# AFE.net
KiCad netlist of a schematic drawn in Altium Designer
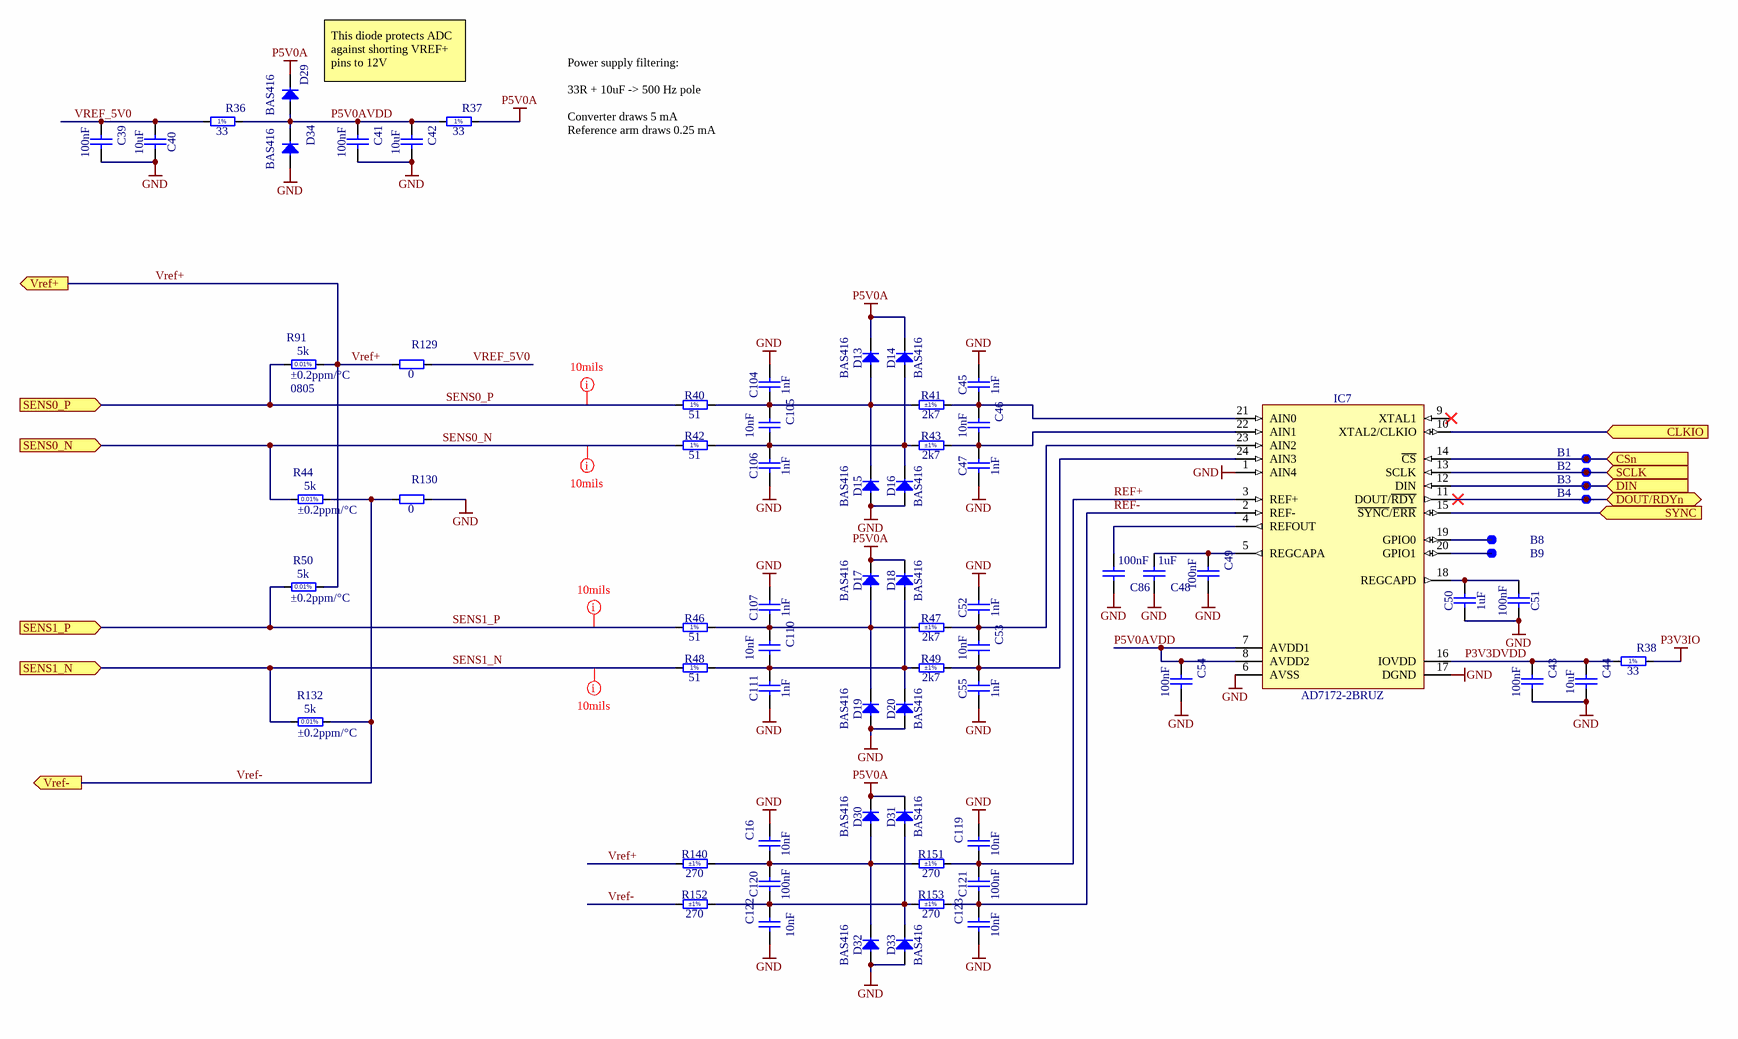
[diagram p0: AFE.SchDoc]

(export (version "E")
  (design (tool "Eeschema 10.0.6"))
  (components
    (comp (ref "B1")
      (value "SMD Pad")
      (footprint "C100")
      (description "Through Hole Pad")
      (fields (field (name "PART NUMBER") "SMD_PAD_D1MM") (field (name "AUTHOR") "CERN DEM JLC"))
      (libsource (lib "Eletro-mechanical") (part "Single SMD Pad (Round)"))
    )
    (comp (ref "B2")
      (value "SMD Pad")
      (footprint "C100")
      (description "Through Hole Pad")
      (fields (field (name "PART NUMBER") "SMD_PAD_D1MM") (field (name "AUTHOR") "CERN DEM JLC"))
      (libsource (lib "Eletro-mechanical") (part "Single SMD Pad (Round)"))
    )
    (comp (ref "B3")
      (value "SMD Pad")
      (footprint "C100")
      (description "Through Hole Pad")
      (fields (field (name "PART NUMBER") "SMD_PAD_D1MM") (field (name "AUTHOR") "CERN DEM JLC"))
      (libsource (lib "Eletro-mechanical") (part "Single SMD Pad (Round)"))
    )
    (comp (ref "B4")
      (value "SMD Pad")
      (footprint "C100")
      (description "Through Hole Pad")
      (fields (field (name "PART NUMBER") "SMD_PAD_D1MM") (field (name "AUTHOR") "CERN DEM JLC"))
      (libsource (lib "Eletro-mechanical") (part "Single SMD Pad (Round)"))
    )
    (comp (ref "B8")
      (value "SMD Pad")
      (footprint "C100")
      (description "Through Hole Pad")
      (fields (field (name "PART NUMBER") "SMD_PAD_D1MM") (field (name "AUTHOR") "CERN DEM JLC"))
      (libsource (lib "Eletro-mechanical") (part "Single SMD Pad (Round)"))
    )
    (comp (ref "B9")
      (value "SMD Pad")
      (footprint "C100")
      (description "Through Hole Pad")
      (fields (field (name "PART NUMBER") "SMD_PAD_D1MM") (field (name "AUTHOR") "CERN DEM JLC"))
      (libsource (lib "Eletro-mechanical") (part "Single SMD Pad (Round)"))
    )
    (comp (ref "C16")
      (value "10nF")
      (footprint "CAPC1608X87N")
      (description "Non-polarised capacitor")
      (fields
        (field (name "PART NUMBER") "CC0603_10NF_50V_5%_C0G")
        (field (name "VOLTAGE") "50V")
        (field (name "AUTHOR") "CERN DEM JLC")
      )
      (libsource (lib "Capacitors") (part "Capacitor - non polarized"))
    )
    (comp (ref "C39")
      (value "100nF")
      (footprint "CAPC1005X55N")
      (description "Non-polarised capacitor")
      (fields
        (field (name "PART NUMBER") "CC0402_100NF_16V_10%_X5R")
        (field (name "VOLTAGE") "16V")
        (field (name "AUTHOR") "CERN DEM JLC")
      )
      (libsource (lib "Capacitors") (part "Capacitor - non polarized"))
    )
    (comp (ref "C40")
      (value "10uF")
      (footprint "CAPC2012X135N")
      (description "Non-polarised capacitor")
      (fields
        (field (name "PART NUMBER") "CC0805_10UF_16V_10%_X5R")
        (field (name "VOLTAGE") "16V")
        (field (name "AUTHOR") "CERN DEM JLC")
      )
      (libsource (lib "Capacitors") (part "Capacitor - non polarized"))
    )
    (comp (ref "C41")
      (value "100nF")
      (footprint "CAPC1005X55N")
      (description "Non-polarised capacitor")
      (fields
        (field (name "PART NUMBER") "CC0402_100NF_16V_10%_X5R")
        (field (name "VOLTAGE") "16V")
        (field (name "AUTHOR") "CERN DEM JLC")
      )
      (libsource (lib "Capacitors") (part "Capacitor - non polarized"))
    )
    (comp (ref "C42")
      (value "10uF")
      (footprint "CAPC2012X135N")
      (description "Non-polarised capacitor")
      (fields
        (field (name "PART NUMBER") "CC0805_10UF_16V_10%_X5R")
        (field (name "VOLTAGE") "16V")
        (field (name "AUTHOR") "CERN DEM JLC")
      )
      (libsource (lib "Capacitors") (part "Capacitor - non polarized"))
    )
    (comp (ref "C43")
      (value "100nF")
      (footprint "CAPC1005X55N")
      (description "Non-polarised capacitor")
      (fields
        (field (name "PART NUMBER") "CC0402_100NF_16V_10%_X5R")
        (field (name "VOLTAGE") "16V")
        (field (name "AUTHOR") "CERN DEM JLC")
      )
      (libsource (lib "Capacitors") (part "Capacitor - non polarized"))
    )
    (comp (ref "C44")
      (value "10uF")
      (footprint "CAPC2012X135N")
      (description "Non-polarised capacitor")
      (fields
        (field (name "PART NUMBER") "CC0805_10UF_16V_10%_X5R")
        (field (name "VOLTAGE") "16V")
        (field (name "AUTHOR") "CERN DEM JLC")
      )
      (libsource (lib "Capacitors") (part "Capacitor - non polarized"))
    )
    (comp (ref "C45")
      (value "1nF")
      (footprint "CAPC1608X90N")
      (description "Non-polarised capacitor")
      (fields
        (field (name "PART NUMBER") "CC0603_1NF_50V_5%_NP0")
        (field (name "VOLTAGE") "50V")
        (field (name "AUTHOR") "CERN DEM JLC")
      )
      (libsource (lib "Capacitors") (part "Capacitor - non polarized"))
    )
    (comp (ref "C46")
      (value "10nF")
      (footprint "CAPC1608X87N")
      (description "Non-polarised capacitor")
      (fields
        (field (name "PART NUMBER") "CC0603_10NF_50V_5%_C0G")
        (field (name "VOLTAGE") "50V")
        (field (name "AUTHOR") "CERN DEM JLC")
      )
      (libsource (lib "Capacitors") (part "Capacitor - non polarized"))
    )
    (comp (ref "C47")
      (value "1nF")
      (footprint "CAPC1608X90N")
      (description "Non-polarised capacitor")
      (fields
        (field (name "PART NUMBER") "CC0603_1NF_50V_5%_NP0")
        (field (name "VOLTAGE") "50V")
        (field (name "AUTHOR") "CERN DEM JLC")
      )
      (libsource (lib "Capacitors") (part "Capacitor - non polarized"))
    )
    (comp (ref "C48")
      (value "1uF")
      (footprint "CAPC1608X87N")
      (description "Non-polarised capacitor")
      (fields
        (field (name "PART NUMBER") "CC0603_1UF_25V_10%_X7R")
        (field (name "VOLTAGE") "25V")
        (field (name "AUTHOR") "CERN DEM JLC")
      )
      (libsource (lib "Capacitors") (part "Capacitor - non polarized"))
    )
    (comp (ref "C49")
      (value "100nF")
      (footprint "CAPC1005X55N")
      (description "Non-polarised capacitor")
      (fields
        (field (name "PART NUMBER") "CC0402_100NF_16V_10%_X5R")
        (field (name "VOLTAGE") "16V")
        (field (name "AUTHOR") "CERN DEM JLC")
      )
      (libsource (lib "Capacitors") (part "Capacitor - non polarized"))
    )
    (comp (ref "C50")
      (value "1uF")
      (footprint "CAPC1608X87N")
      (description "Non-polarised capacitor")
      (fields
        (field (name "PART NUMBER") "CC0603_1UF_25V_10%_X7R")
        (field (name "VOLTAGE") "25V")
        (field (name "AUTHOR") "CERN DEM JLC")
      )
      (libsource (lib "Capacitors") (part "Capacitor - non polarized"))
    )
    (comp (ref "C51")
      (value "100nF")
      (footprint "CAPC1005X55N")
      (description "Non-polarised capacitor")
      (fields
        (field (name "PART NUMBER") "CC0402_100NF_16V_10%_X5R")
        (field (name "VOLTAGE") "16V")
        (field (name "AUTHOR") "CERN DEM JLC")
      )
      (libsource (lib "Capacitors") (part "Capacitor - non polarized"))
    )
    (comp (ref "C52")
      (value "1nF")
      (footprint "CAPC1608X90N")
      (description "Non-polarised capacitor")
      (fields
        (field (name "PART NUMBER") "CC0603_1NF_50V_5%_NP0")
        (field (name "VOLTAGE") "50V")
        (field (name "AUTHOR") "CERN DEM JLC")
      )
      (libsource (lib "Capacitors") (part "Capacitor - non polarized"))
    )
    (comp (ref "C53")
      (value "10nF")
      (footprint "CAPC1608X87N")
      (description "Non-polarised capacitor")
      (fields
        (field (name "PART NUMBER") "CC0603_10NF_50V_5%_C0G")
        (field (name "VOLTAGE") "50V")
        (field (name "AUTHOR") "CERN DEM JLC")
      )
      (libsource (lib "Capacitors") (part "Capacitor - non polarized"))
    )
    (comp (ref "C54")
      (value "100nF")
      (footprint "CAPC1005X55N")
      (description "Non-polarised capacitor")
      (fields
        (field (name "PART NUMBER") "CC0402_100NF_16V_10%_X5R")
        (field (name "VOLTAGE") "16V")
        (field (name "AUTHOR") "CERN DEM JLC")
      )
      (libsource (lib "Capacitors") (part "Capacitor - non polarized"))
    )
    (comp (ref "C55")
      (value "1nF")
      (footprint "CAPC1608X90N")
      (description "Non-polarised capacitor")
      (fields
        (field (name "PART NUMBER") "CC0603_1NF_50V_5%_NP0")
        (field (name "VOLTAGE") "50V")
        (field (name "AUTHOR") "CERN DEM JLC")
      )
      (libsource (lib "Capacitors") (part "Capacitor - non polarized"))
    )
    (comp (ref "C86")
      (value "100nF")
      (footprint "CAPC1005X55N")
      (description "Non-polarised capacitor")
      (fields
        (field (name "PART NUMBER") "CC0402_100NF_16V_10%_X5R")
        (field (name "VOLTAGE") "16V")
        (field (name "AUTHOR") "CERN DEM JLC")
      )
      (libsource (lib "Capacitors") (part "Capacitor - non polarized"))
    )
    (comp (ref "C104")
      (value "1nF")
      (footprint "CAPC1608X90N")
      (description "Non-polarised capacitor")
      (fields
        (field (name "PART NUMBER") "CC0603_1NF_50V_5%_NP0")
        (field (name "VOLTAGE") "50V")
        (field (name "AUTHOR") "CERN DEM JLC")
      )
      (libsource (lib "Capacitors") (part "Capacitor - non polarized"))
    )
    (comp (ref "C105")
      (value "10nF")
      (footprint "CAPC1608X87N")
      (description "Non-polarised capacitor")
      (fields
        (field (name "PART NUMBER") "CC0603_10NF_50V_5%_C0G")
        (field (name "VOLTAGE") "50V")
        (field (name "AUTHOR") "CERN DEM JLC")
      )
      (libsource (lib "Capacitors") (part "Capacitor - non polarized"))
    )
    (comp (ref "C106")
      (value "1nF")
      (footprint "CAPC1608X90N")
      (description "Non-polarised capacitor")
      (fields
        (field (name "PART NUMBER") "CC0603_1NF_50V_5%_NP0")
        (field (name "VOLTAGE") "50V")
        (field (name "AUTHOR") "CERN DEM JLC")
      )
      (libsource (lib "Capacitors") (part "Capacitor - non polarized"))
    )
    (comp (ref "C107")
      (value "1nF")
      (footprint "CAPC1608X90N")
      (description "Non-polarised capacitor")
      (fields
        (field (name "PART NUMBER") "CC0603_1NF_50V_5%_NP0")
        (field (name "VOLTAGE") "50V")
        (field (name "AUTHOR") "CERN DEM JLC")
      )
      (libsource (lib "Capacitors") (part "Capacitor - non polarized"))
    )
    (comp (ref "C110")
      (value "10nF")
      (footprint "CAPC1608X87N")
      (description "Non-polarised capacitor")
      (fields
        (field (name "PART NUMBER") "CC0603_10NF_50V_5%_C0G")
        (field (name "VOLTAGE") "50V")
        (field (name "AUTHOR") "CERN DEM JLC")
      )
      (libsource (lib "Capacitors") (part "Capacitor - non polarized"))
    )
    (comp (ref "C111")
      (value "1nF")
      (footprint "CAPC1608X90N")
      (description "Non-polarised capacitor")
      (fields
        (field (name "PART NUMBER") "CC0603_1NF_50V_5%_NP0")
        (field (name "VOLTAGE") "50V")
        (field (name "AUTHOR") "CERN DEM JLC")
      )
      (libsource (lib "Capacitors") (part "Capacitor - non polarized"))
    )
    (comp (ref "C119")
      (value "10nF")
      (footprint "CAPC1608X87N")
      (description "Non-polarised capacitor")
      (fields
        (field (name "PART NUMBER") "CC0603_10NF_50V_5%_C0G")
        (field (name "VOLTAGE") "50V")
        (field (name "AUTHOR") "CERN DEM JLC")
      )
      (libsource (lib "Capacitors") (part "Capacitor - non polarized"))
    )
    (comp (ref "C120")
      (value "100nF")
      (footprint "CAPC1608X87N")
      (description "Non-polarised capacitor")
      (fields
        (field (name "PART NUMBER") "CC0603_100NF_50V_10%_X5R")
        (field (name "VOLTAGE") "50V")
        (field (name "AUTHOR") "CERN DEM MR")
      )
      (libsource (lib "Capacitors") (part "Capacitor - non polarized"))
    )
    (comp (ref "C121")
      (value "100nF")
      (footprint "CAPC1608X87N")
      (description "Non-polarised capacitor")
      (fields
        (field (name "PART NUMBER") "CC0603_100NF_50V_10%_X5R")
        (field (name "VOLTAGE") "50V")
        (field (name "AUTHOR") "CERN DEM MR")
      )
      (libsource (lib "Capacitors") (part "Capacitor - non polarized"))
    )
    (comp (ref "C122")
      (value "10nF")
      (footprint "CAPC1608X87N")
      (description "Non-polarised capacitor")
      (fields
        (field (name "PART NUMBER") "CC0603_10NF_50V_5%_C0G")
        (field (name "VOLTAGE") "50V")
        (field (name "AUTHOR") "CERN DEM JLC")
      )
      (libsource (lib "Capacitors") (part "Capacitor - non polarized"))
    )
    (comp (ref "C123")
      (value "10nF")
      (footprint "CAPC1608X87N")
      (description "Non-polarised capacitor")
      (fields
        (field (name "PART NUMBER") "CC0603_10NF_50V_5%_C0G")
        (field (name "VOLTAGE") "50V")
        (field (name "AUTHOR") "CERN DEM JLC")
      )
      (libsource (lib "Capacitors") (part "Capacitor - non polarized"))
    )
    (comp (ref "D13")
      (value "BAS416")
      (footprint "SOD2512X110N")
      (description "Diode")
      (fields
        (field (name "VOLTAGE") "75V")
        (field (name "POWER") "200mA")
        (field (name "AUTHOR") "CERN DEM JLC")
      )
      (libsource (lib "ICs And Semiconductors") (part "Diode"))
    )
    (comp (ref "D14")
      (value "BAS416")
      (footprint "SOD2512X110N")
      (description "Diode")
      (fields
        (field (name "VOLTAGE") "75V")
        (field (name "POWER") "200mA")
        (field (name "AUTHOR") "CERN DEM JLC")
      )
      (libsource (lib "ICs And Semiconductors") (part "Diode"))
    )
    (comp (ref "D15")
      (value "BAS416")
      (footprint "SOD2512X110N")
      (description "Diode")
      (fields
        (field (name "VOLTAGE") "75V")
        (field (name "POWER") "200mA")
        (field (name "AUTHOR") "CERN DEM JLC")
      )
      (libsource (lib "ICs And Semiconductors") (part "Diode"))
    )
    (comp (ref "D16")
      (value "BAS416")
      (footprint "SOD2512X110N")
      (description "Diode")
      (fields
        (field (name "VOLTAGE") "75V")
        (field (name "POWER") "200mA")
        (field (name "AUTHOR") "CERN DEM JLC")
      )
      (libsource (lib "ICs And Semiconductors") (part "Diode"))
    )
    (comp (ref "D17")
      (value "BAS416")
      (footprint "SOD2512X110N")
      (description "Diode")
      (fields
        (field (name "VOLTAGE") "75V")
        (field (name "POWER") "200mA")
        (field (name "AUTHOR") "CERN DEM JLC")
      )
      (libsource (lib "ICs And Semiconductors") (part "Diode"))
    )
    (comp (ref "D18")
      (value "BAS416")
      (footprint "SOD2512X110N")
      (description "Diode")
      (fields
        (field (name "VOLTAGE") "75V")
        (field (name "POWER") "200mA")
        (field (name "AUTHOR") "CERN DEM JLC")
      )
      (libsource (lib "ICs And Semiconductors") (part "Diode"))
    )
    (comp (ref "D19")
      (value "BAS416")
      (footprint "SOD2512X110N")
      (description "Diode")
      (fields
        (field (name "VOLTAGE") "75V")
        (field (name "POWER") "200mA")
        (field (name "AUTHOR") "CERN DEM JLC")
      )
      (libsource (lib "ICs And Semiconductors") (part "Diode"))
    )
    (comp (ref "D20")
      (value "BAS416")
      (footprint "SOD2512X110N")
      (description "Diode")
      (fields
        (field (name "VOLTAGE") "75V")
        (field (name "POWER") "200mA")
        (field (name "AUTHOR") "CERN DEM JLC")
      )
      (libsource (lib "ICs And Semiconductors") (part "Diode"))
    )
    (comp (ref "D29")
      (value "BAS416")
      (footprint "SOD2512X110N")
      (description "Diode")
      (fields
        (field (name "VOLTAGE") "75V")
        (field (name "POWER") "200mA")
        (field (name "AUTHOR") "CERN DEM JLC")
      )
      (libsource (lib "ICs And Semiconductors") (part "Diode"))
    )
    (comp (ref "D30")
      (value "BAS416")
      (footprint "SOD2512X110N")
      (description "Diode")
      (fields
        (field (name "VOLTAGE") "75V")
        (field (name "POWER") "200mA")
        (field (name "AUTHOR") "CERN DEM JLC")
      )
      (libsource (lib "ICs And Semiconductors") (part "Diode"))
    )
    (comp (ref "D31")
      (value "BAS416")
      (footprint "SOD2512X110N")
      (description "Diode")
      (fields
        (field (name "VOLTAGE") "75V")
        (field (name "POWER") "200mA")
        (field (name "AUTHOR") "CERN DEM JLC")
      )
      (libsource (lib "ICs And Semiconductors") (part "Diode"))
    )
    (comp (ref "D32")
      (value "BAS416")
      (footprint "SOD2512X110N")
      (description "Diode")
      (fields
        (field (name "VOLTAGE") "75V")
        (field (name "POWER") "200mA")
        (field (name "AUTHOR") "CERN DEM JLC")
      )
      (libsource (lib "ICs And Semiconductors") (part "Diode"))
    )
    (comp (ref "D33")
      (value "BAS416")
      (footprint "SOD2512X110N")
      (description "Diode")
      (fields
        (field (name "VOLTAGE") "75V")
        (field (name "POWER") "200mA")
        (field (name "AUTHOR") "CERN DEM JLC")
      )
      (libsource (lib "ICs And Semiconductors") (part "Diode"))
    )
    (comp (ref "D34")
      (value "BAS416")
      (footprint "SOD2512X110N")
      (description "Diode")
      (fields
        (field (name "VOLTAGE") "75V")
        (field (name "POWER") "200mA")
        (field (name "AUTHOR") "CERN DEM JLC")
      )
      (libsource (lib "ICs And Semiconductors") (part "Diode"))
    )
    (comp (ref "IC7")
      (value "AD7172-2BRUZ")
      (footprint "SOP65P640X120-24N")
      (description "32-Bit, 10 kSPS, Sigma-Delta ADC with 100 µs Settling and True Rail-to-Rail Buffers")
      (fields (field (name "MANUFACTURER") "ANALOG DEVICES") (field (name "AUTHOR") "GK"))
      (libsource (lib "LIBRARY_SCH") (part "ADC_AD7172-2"))
    )
    (comp (ref "R36")
      (value "33")
      (footprint "RESC1005X40N")
      (description "Resistor - 1%")
      (fields
        (field (name "PART NUMBER") "R0402_33R_1%_0.0625W_100PPM")
        (field (name "POWER") "0.0625W")
        (field (name "AUTHOR") "CERN DEM JLC")
      )
      (libsource (lib "Resistors") (part "Resistor - 1%"))
    )
    (comp (ref "R37")
      (value "33")
      (footprint "RESC1005X40N")
      (description "Resistor - 1%")
      (fields
        (field (name "PART NUMBER") "R0402_33R_1%_0.0625W_100PPM")
        (field (name "POWER") "0.0625W")
        (field (name "AUTHOR") "CERN DEM JLC")
      )
      (libsource (lib "Resistors") (part "Resistor - 1%"))
    )
    (comp (ref "R38")
      (value "33")
      (footprint "RESC1005X40N")
      (description "Resistor - 1%")
      (fields
        (field (name "PART NUMBER") "R0402_33R_1%_0.0625W_100PPM")
        (field (name "POWER") "0.0625W")
        (field (name "AUTHOR") "CERN DEM JLC")
      )
      (libsource (lib "Resistors") (part "Resistor - 1%"))
    )
    (comp (ref "R40")
      (value "51")
      (footprint "RESC1005X40N")
      (description "Resistor - 1%")
      (fields
        (field (name "PART NUMBER") "R0402_51R_1%_0.0625W_100PPM")
        (field (name "POWER") "0.0625W")
        (field (name "AUTHOR") "CERN DEM JLC")
      )
      (libsource (lib "Resistors") (part "Resistor - 1%"))
    )
    (comp (ref "R41")
      (value "2k7")
      (footprint "RESC1005X40N")
      (description "Resistor - 1%")
      (fields
        (field (name "TOLERANCE") "±1%")
        (field (name "PART NUMBER") "R0402_2K7_1%_0.0625W_100PPM")
        (field (name "POWER") "0.0625W")
        (field (name "AUTHOR") "CERN DEM JLC")
      )
      (libsource (lib "Resistors") (part "Resistor - 1%"))
    )
    (comp (ref "R42")
      (value "51")
      (footprint "RESC1005X40N")
      (description "Resistor - 1%")
      (fields
        (field (name "PART NUMBER") "R0402_51R_1%_0.0625W_100PPM")
        (field (name "POWER") "0.0625W")
        (field (name "AUTHOR") "CERN DEM JLC")
      )
      (libsource (lib "Resistors") (part "Resistor - 1%"))
    )
    (comp (ref "R43")
      (value "2k7")
      (footprint "RESC1005X40N")
      (description "Resistor - 1%")
      (fields
        (field (name "TOLERANCE") "±1%")
        (field (name "PART NUMBER") "R0402_2K7_1%_0.0625W_100PPM")
        (field (name "POWER") "0.0625W")
        (field (name "AUTHOR") "CERN DEM JLC")
      )
      (libsource (lib "Resistors") (part "Resistor - 1%"))
    )
    (comp (ref "R44")
      (value "5k")
      (footprint "RESC2013X64N")
      (description "Resistor - 0.01%")
      (fields
        (field (name "PART NUMBER") "R0805_5K_0.01%_0.2W_0.2PPM_VISHAY_VSMP")
        (field (name "POWER") "0.2W")
        (field (name "TC") "±0.2ppm/°C")
        (field (name "AUTHOR") "CERN DEM JLC")
      )
      (libsource (lib "Resistors") (part "Resistor - 0.01%"))
    )
    (comp (ref "R46")
      (value "51")
      (footprint "RESC1005X40N")
      (description "Resistor - 1%")
      (fields
        (field (name "PART NUMBER") "R0402_51R_1%_0.0625W_100PPM")
        (field (name "POWER") "0.0625W")
        (field (name "AUTHOR") "CERN DEM JLC")
      )
      (libsource (lib "Resistors") (part "Resistor - 1%"))
    )
    (comp (ref "R47")
      (value "2k7")
      (footprint "RESC1005X40N")
      (description "Resistor - 1%")
      (fields
        (field (name "TOLERANCE") "±1%")
        (field (name "PART NUMBER") "R0402_2K7_1%_0.0625W_100PPM")
        (field (name "POWER") "0.0625W")
        (field (name "AUTHOR") "CERN DEM JLC")
      )
      (libsource (lib "Resistors") (part "Resistor - 1%"))
    )
    (comp (ref "R48")
      (value "51")
      (footprint "RESC1005X40N")
      (description "Resistor - 1%")
      (fields
        (field (name "PART NUMBER") "R0402_51R_1%_0.0625W_100PPM")
        (field (name "POWER") "0.0625W")
        (field (name "AUTHOR") "CERN DEM JLC")
      )
      (libsource (lib "Resistors") (part "Resistor - 1%"))
    )
    (comp (ref "R49")
      (value "2k7")
      (footprint "RESC1005X40N")
      (description "Resistor - 1%")
      (fields
        (field (name "TOLERANCE") "±1%")
        (field (name "PART NUMBER") "R0402_2K7_1%_0.0625W_100PPM")
        (field (name "POWER") "0.0625W")
        (field (name "AUTHOR") "CERN DEM JLC")
      )
      (libsource (lib "Resistors") (part "Resistor - 1%"))
    )
    (comp (ref "R50")
      (value "5k")
      (footprint "RESC2013X64N")
      (description "Resistor - 0.01%")
      (fields
        (field (name "PART NUMBER") "R0805_5K_0.01%_0.2W_0.2PPM_VISHAY_VSMP")
        (field (name "POWER") "0.2W")
        (field (name "TC") "±0.2ppm/°C")
        (field (name "AUTHOR") "CERN DEM JLC")
      )
      (libsource (lib "Resistors") (part "Resistor - 0.01%"))
    )
    (comp (ref "R91")
      (value "5k")
      (footprint "RESC2013X64N")
      (description "Resistor - 0.01%")
      (fields
        (field (name "PART NUMBER") "R0805_5K_0.01%_0.2W_0.2PPM_VISHAY_VSMP")
        (field (name "POWER") "0.2W")
        (field (name "TC") "±0.2ppm/°C")
        (field (name "CASE") "0805")
        (field (name "AUTHOR") "CERN DEM JLC")
      )
      (libsource (lib "Resistors") (part "Resistor - 0.01%"))
    )
    (comp (ref "R129")
      (value "0")
      (footprint "RESC1608X55N")
      (description "Resistor")
      (fields
        (field (name "PART NUMBER") "R0603_0R_JUMPER")
        (field (name "MANUFACTURER") "GENERIC")
        (field (name "AUTHOR") "CERN DEM JLC")
      )
      (libsource (lib "Resistors") (part "Resistor"))
    )
    (comp (ref "R130")
      (value "0")
      (footprint "RESC1608X55N")
      (description "Resistor")
      (fields
        (field (name "PART NUMBER") "R0603_0R_JUMPER")
        (field (name "MANUFACTURER") "GENERIC")
        (field (name "AUTHOR") "CERN DEM JLC")
      )
      (libsource (lib "Resistors") (part "Resistor"))
    )
    (comp (ref "R132")
      (value "5k")
      (footprint "RESC2013X64N")
      (description "Resistor - 0.01%")
      (fields
        (field (name "PART NUMBER") "R0805_5K_0.01%_0.2W_0.2PPM_VISHAY_VSMP")
        (field (name "POWER") "0.2W")
        (field (name "TC") "±0.2ppm/°C")
        (field (name "AUTHOR") "CERN DEM JLC")
      )
      (libsource (lib "Resistors") (part "Resistor - 0.01%"))
    )
    (comp (ref "R140")
      (value "270")
      (footprint "RESC1005X40N")
      (description "Resistor - 1%")
      (fields
        (field (name "TOLERANCE") "±1%")
        (field (name "PART NUMBER") "R0402_270R_1%_0.0625W_100PPM")
        (field (name "POWER") "0.0625W")
        (field (name "AUTHOR") "CERN DEM JLC")
      )
      (libsource (lib "Resistors") (part "Resistor - 1%"))
    )
    (comp (ref "R151")
      (value "270")
      (footprint "RESC1005X40N")
      (description "Resistor - 1%")
      (fields
        (field (name "TOLERANCE") "±1%")
        (field (name "PART NUMBER") "R0402_270R_1%_0.0625W_100PPM")
        (field (name "POWER") "0.0625W")
        (field (name "AUTHOR") "CERN DEM JLC")
      )
      (libsource (lib "Resistors") (part "Resistor - 1%"))
    )
    (comp (ref "R152")
      (value "270")
      (footprint "RESC1005X40N")
      (description "Resistor - 1%")
      (fields
        (field (name "TOLERANCE") "±1%")
        (field (name "PART NUMBER") "R0402_270R_1%_0.0625W_100PPM")
        (field (name "POWER") "0.0625W")
        (field (name "AUTHOR") "CERN DEM JLC")
      )
      (libsource (lib "Resistors") (part "Resistor - 1%"))
    )
    (comp (ref "R153")
      (value "270")
      (footprint "RESC1005X40N")
      (description "Resistor - 1%")
      (fields
        (field (name "TOLERANCE") "±1%")
        (field (name "PART NUMBER") "R0402_270R_1%_0.0625W_100PPM")
        (field (name "POWER") "0.0625W")
        (field (name "AUTHOR") "CERN DEM JLC")
      )
      (libsource (lib "Resistors") (part "Resistor - 1%"))
    )
  )
  (nets
    (net (code "1") (name "/CLKIO") (class "Default")
      (node (ref "IC7") (pin "10") (pinfunction "XTAL2/CLKIO_10") (pintype "bidirectional"))
    )
    (net (code "2") (name "/CSn") (class "Default")
      (node (ref "B1") (pin "1") (pinfunction "1_1") (pintype "bidirectional"))
      (node (ref "IC7") (pin "14") (pinfunction "~{CS}_14") (pintype "input"))
    )
    (net (code "3") (name "/DIN") (class "Default")
      (node (ref "B3") (pin "1") (pinfunction "1_1") (pintype "bidirectional"))
      (node (ref "IC7") (pin "12") (pinfunction "DIN_12") (pintype "input"))
    )
    (net (code "4") (name "/DOUT{slash}RDYn") (class "Default")
      (node (ref "B4") (pin "1") (pinfunction "1_1") (pintype "bidirectional"))
      (node (ref "IC7") (pin "11") (pinfunction "DOUT/~{RDY}_11") (pintype "output"))
    )
    (net (code "5") (name "/P3V3DVDD") (class "Default")
      (node (ref "C43") (pin "1") (pinfunction "1_1") (pintype "passive"))
      (node (ref "C44") (pin "1") (pinfunction "1_1") (pintype "passive"))
      (node (ref "IC7") (pin "16") (pinfunction "IOVDD_16") (pintype "power_in"))
      (node (ref "R38") (pin "1") (pinfunction "1_1") (pintype "passive"))
    )
    (net (code "6") (name "/P5V0AVDD") (class "Default")
      (node (ref "C41") (pin "1") (pinfunction "1_1") (pintype "passive"))
      (node (ref "C42") (pin "1") (pinfunction "1_1") (pintype "passive"))
      (node (ref "C54") (pin "1") (pinfunction "1_1") (pintype "passive"))
      (node (ref "D29") (pin "2") (pinfunction "A_2") (pintype "passive"))
      (node (ref "D34") (pin "1") (pinfunction "C_1") (pintype "passive"))
      (node (ref "IC7") (pin "7") (pinfunction "AVDD1_7") (pintype "power_in"))
      (node (ref "IC7") (pin "8") (pinfunction "AVDD2_8") (pintype "power_in"))
      (node (ref "R36") (pin "2") (pinfunction "2_2") (pintype "passive"))
      (node (ref "R37") (pin "1") (pinfunction "1_1") (pintype "passive"))
    )
    (net (code "7") (name "/REF+") (class "Default")
      (node (ref "C119") (pin "1") (pinfunction "1_1") (pintype "passive"))
      (node (ref "C121") (pin "2") (pinfunction "2_2") (pintype "passive"))
      (node (ref "IC7") (pin "3") (pinfunction "REF+_3") (pintype "input"))
      (node (ref "R151") (pin "2") (pinfunction "2_2") (pintype "passive"))
    )
    (net (code "8") (name "/REF-") (class "Default")
      (node (ref "C121") (pin "1") (pinfunction "1_1") (pintype "passive"))
      (node (ref "C123") (pin "2") (pinfunction "2_2") (pintype "passive"))
      (node (ref "IC7") (pin "2") (pinfunction "REF-_2") (pintype "input"))
      (node (ref "R153") (pin "2") (pinfunction "2_2") (pintype "passive"))
    )
    (net (code "9") (name "/SCLK") (class "Default")
      (node (ref "B2") (pin "1") (pinfunction "1_1") (pintype "bidirectional"))
      (node (ref "IC7") (pin "13") (pinfunction "SCLK_13") (pintype "input"))
    )
    (net (code "10") (name "/SENS0_N") (class "Default")
      (node (ref "R42") (pin "1") (pinfunction "1_1") (pintype "passive"))
      (node (ref "R44") (pin "1") (pinfunction "1_1") (pintype "passive"))
    )
    (net (code "11") (name "/SENS0_P") (class "Default")
      (node (ref "R40") (pin "1") (pinfunction "1_1") (pintype "passive"))
      (node (ref "R91") (pin "1") (pinfunction "1_1") (pintype "passive"))
    )
    (net (code "12") (name "/SENS1_N") (class "Default")
      (node (ref "R132") (pin "1") (pinfunction "1_1") (pintype "passive"))
      (node (ref "R48") (pin "1") (pinfunction "1_1") (pintype "passive"))
    )
    (net (code "13") (name "/SENS1_P") (class "Default")
      (node (ref "R46") (pin "1") (pinfunction "1_1") (pintype "passive"))
      (node (ref "R50") (pin "1") (pinfunction "1_1") (pintype "passive"))
    )
    (net (code "14") (name "/SYNC") (class "Default")
      (node (ref "IC7") (pin "15") (pinfunction "~{SYNC}/~{ERR}_15") (pintype "bidirectional"))
    )
    (net (code "15") (name "/VREF_5V0") (class "Default")
      (node (ref "C39") (pin "1") (pinfunction "1_1") (pintype "passive"))
      (node (ref "C40") (pin "1") (pinfunction "1_1") (pintype "passive"))
      (node (ref "R129") (pin "2") (pinfunction "2_2") (pintype "passive"))
      (node (ref "R36") (pin "1") (pinfunction "1_1") (pintype "passive"))
    )
    (net (code "16") (name "/Vref+") (class "Default")
      (node (ref "R129") (pin "1") (pinfunction "1_1") (pintype "passive"))
      (node (ref "R140") (pin "1") (pinfunction "1_1") (pintype "passive"))
      (node (ref "R50") (pin "2") (pinfunction "2_2") (pintype "passive"))
      (node (ref "R91") (pin "2") (pinfunction "2_2") (pintype "passive"))
    )
    (net (code "17") (name "/Vref-") (class "Default")
      (node (ref "R130") (pin "1") (pinfunction "1_1") (pintype "passive"))
      (node (ref "R132") (pin "2") (pinfunction "2_2") (pintype "passive"))
      (node (ref "R152") (pin "1") (pinfunction "1_1") (pintype "passive"))
      (node (ref "R44") (pin "2") (pinfunction "2_2") (pintype "passive"))
    )
    (net (code "18") (name "GND") (class "Default")
      (node (ref "C104") (pin "2") (pinfunction "2_2") (pintype "passive"))
      (node (ref "C106") (pin "1") (pinfunction "1_1") (pintype "passive"))
      (node (ref "C107") (pin "2") (pinfunction "2_2") (pintype "passive"))
      (node (ref "C111") (pin "1") (pinfunction "1_1") (pintype "passive"))
      (node (ref "C119") (pin "2") (pinfunction "2_2") (pintype "passive"))
      (node (ref "C122") (pin "1") (pinfunction "1_1") (pintype "passive"))
      (node (ref "C123") (pin "1") (pinfunction "1_1") (pintype "passive"))
      (node (ref "C16") (pin "2") (pinfunction "2_2") (pintype "passive"))
      (node (ref "C39") (pin "2") (pinfunction "2_2") (pintype "passive"))
      (node (ref "C40") (pin "2") (pinfunction "2_2") (pintype "passive"))
      (node (ref "C41") (pin "2") (pinfunction "2_2") (pintype "passive"))
      (node (ref "C42") (pin "2") (pinfunction "2_2") (pintype "passive"))
      (node (ref "C43") (pin "2") (pinfunction "2_2") (pintype "passive"))
      (node (ref "C44") (pin "2") (pinfunction "2_2") (pintype "passive"))
      (node (ref "C45") (pin "2") (pinfunction "2_2") (pintype "passive"))
      (node (ref "C47") (pin "1") (pinfunction "1_1") (pintype "passive"))
      (node (ref "C48") (pin "1") (pinfunction "1_1") (pintype "passive"))
      (node (ref "C49") (pin "2") (pinfunction "2_2") (pintype "passive"))
      (node (ref "C50") (pin "1") (pinfunction "1_1") (pintype "passive"))
      (node (ref "C51") (pin "2") (pinfunction "2_2") (pintype "passive"))
      (node (ref "C52") (pin "2") (pinfunction "2_2") (pintype "passive"))
      (node (ref "C54") (pin "2") (pinfunction "2_2") (pintype "passive"))
      (node (ref "C55") (pin "1") (pinfunction "1_1") (pintype "passive"))
      (node (ref "C86") (pin "2") (pinfunction "2_2") (pintype "passive"))
      (node (ref "D15") (pin "2") (pinfunction "A_2") (pintype "passive"))
      (node (ref "D16") (pin "2") (pinfunction "A_2") (pintype "passive"))
      (node (ref "D19") (pin "2") (pinfunction "A_2") (pintype "passive"))
      (node (ref "D20") (pin "2") (pinfunction "A_2") (pintype "passive"))
      (node (ref "D32") (pin "2") (pinfunction "A_2") (pintype "passive"))
      (node (ref "D33") (pin "2") (pinfunction "A_2") (pintype "passive"))
      (node (ref "D34") (pin "2") (pinfunction "A_2") (pintype "passive"))
      (node (ref "IC7") (pin "1") (pinfunction "AIN4_1") (pintype "input"))
      (node (ref "IC7") (pin "17") (pinfunction "DGND_17") (pintype "power_in"))
      (node (ref "IC7") (pin "6") (pinfunction "AVSS_6") (pintype "power_in"))
      (node (ref "R130") (pin "2") (pinfunction "2_2") (pintype "passive"))
    )
    (net (code "19") (name "Net-(D13-A)") (class "Default")
      (node (ref "C104") (pin "1") (pinfunction "1_1") (pintype "passive"))
      (node (ref "C105") (pin "1") (pinfunction "1_1") (pintype "passive"))
      (node (ref "D13") (pin "2") (pinfunction "A_2") (pintype "passive"))
      (node (ref "D15") (pin "1") (pinfunction "C_1") (pintype "passive"))
      (node (ref "R40") (pin "2") (pinfunction "2_2") (pintype "passive"))
      (node (ref "R41") (pin "1") (pinfunction "1_1") (pintype "passive"))
    )
    (net (code "20") (name "Net-(D14-A)") (class "Default")
      (node (ref "C105") (pin "2") (pinfunction "2_2") (pintype "passive"))
      (node (ref "C106") (pin "2") (pinfunction "2_2") (pintype "passive"))
      (node (ref "D14") (pin "2") (pinfunction "A_2") (pintype "passive"))
      (node (ref "D16") (pin "1") (pinfunction "C_1") (pintype "passive"))
      (node (ref "R42") (pin "2") (pinfunction "2_2") (pintype "passive"))
      (node (ref "R43") (pin "1") (pinfunction "1_1") (pintype "passive"))
    )
    (net (code "21") (name "Net-(D17-A)") (class "Default")
      (node (ref "C107") (pin "1") (pinfunction "1_1") (pintype "passive"))
      (node (ref "C110") (pin "1") (pinfunction "1_1") (pintype "passive"))
      (node (ref "D17") (pin "2") (pinfunction "A_2") (pintype "passive"))
      (node (ref "D19") (pin "1") (pinfunction "C_1") (pintype "passive"))
      (node (ref "R46") (pin "2") (pinfunction "2_2") (pintype "passive"))
      (node (ref "R47") (pin "1") (pinfunction "1_1") (pintype "passive"))
    )
    (net (code "22") (name "Net-(D18-A)") (class "Default")
      (node (ref "C110") (pin "2") (pinfunction "2_2") (pintype "passive"))
      (node (ref "C111") (pin "2") (pinfunction "2_2") (pintype "passive"))
      (node (ref "D18") (pin "2") (pinfunction "A_2") (pintype "passive"))
      (node (ref "D20") (pin "1") (pinfunction "C_1") (pintype "passive"))
      (node (ref "R48") (pin "2") (pinfunction "2_2") (pintype "passive"))
      (node (ref "R49") (pin "1") (pinfunction "1_1") (pintype "passive"))
    )
    (net (code "23") (name "Net-(D30-A)") (class "Default")
      (node (ref "C120") (pin "2") (pinfunction "2_2") (pintype "passive"))
      (node (ref "C16") (pin "1") (pinfunction "1_1") (pintype "passive"))
      (node (ref "D30") (pin "2") (pinfunction "A_2") (pintype "passive"))
      (node (ref "D32") (pin "1") (pinfunction "C_1") (pintype "passive"))
      (node (ref "R140") (pin "2") (pinfunction "2_2") (pintype "passive"))
      (node (ref "R151") (pin "1") (pinfunction "1_1") (pintype "passive"))
    )
    (net (code "24") (name "Net-(D31-A)") (class "Default")
      (node (ref "C120") (pin "1") (pinfunction "1_1") (pintype "passive"))
      (node (ref "C122") (pin "2") (pinfunction "2_2") (pintype "passive"))
      (node (ref "D31") (pin "2") (pinfunction "A_2") (pintype "passive"))
      (node (ref "D33") (pin "1") (pinfunction "C_1") (pintype "passive"))
      (node (ref "R152") (pin "2") (pinfunction "2_2") (pintype "passive"))
      (node (ref "R153") (pin "1") (pinfunction "1_1") (pintype "passive"))
    )
    (net (code "25") (name "Net-(IC7-AIN0)") (class "Default")
      (node (ref "C45") (pin "1") (pinfunction "1_1") (pintype "passive"))
      (node (ref "C46") (pin "1") (pinfunction "1_1") (pintype "passive"))
      (node (ref "IC7") (pin "21") (pinfunction "AIN0_21") (pintype "input"))
      (node (ref "R41") (pin "2") (pinfunction "2_2") (pintype "passive"))
    )
    (net (code "26") (name "Net-(IC7-AIN1)") (class "Default")
      (node (ref "C46") (pin "2") (pinfunction "2_2") (pintype "passive"))
      (node (ref "C47") (pin "2") (pinfunction "2_2") (pintype "passive"))
      (node (ref "IC7") (pin "22") (pinfunction "AIN1_22") (pintype "input"))
      (node (ref "R43") (pin "2") (pinfunction "2_2") (pintype "passive"))
    )
    (net (code "27") (name "Net-(IC7-AIN2)") (class "Default")
      (node (ref "C52") (pin "1") (pinfunction "1_1") (pintype "passive"))
      (node (ref "C53") (pin "1") (pinfunction "1_1") (pintype "passive"))
      (node (ref "IC7") (pin "23") (pinfunction "AIN2_23") (pintype "input"))
      (node (ref "R47") (pin "2") (pinfunction "2_2") (pintype "passive"))
    )
    (net (code "28") (name "Net-(IC7-AIN3)") (class "Default")
      (node (ref "C53") (pin "2") (pinfunction "2_2") (pintype "passive"))
      (node (ref "C55") (pin "2") (pinfunction "2_2") (pintype "passive"))
      (node (ref "IC7") (pin "24") (pinfunction "AIN3_24") (pintype "input"))
      (node (ref "R49") (pin "2") (pinfunction "2_2") (pintype "passive"))
    )
    (net (code "29") (name "Net-(IC7-GPIO0)") (class "Default")
      (node (ref "B8") (pin "1") (pinfunction "1_1") (pintype "bidirectional"))
      (node (ref "IC7") (pin "19") (pinfunction "GPIO0_19") (pintype "bidirectional"))
    )
    (net (code "30") (name "Net-(IC7-GPIO1)") (class "Default")
      (node (ref "B9") (pin "1") (pinfunction "1_1") (pintype "bidirectional"))
      (node (ref "IC7") (pin "20") (pinfunction "GPIO1_20") (pintype "bidirectional"))
    )
    (net (code "31") (name "Net-(IC7-REFOUT)") (class "Default")
      (node (ref "C86") (pin "1") (pinfunction "1_1") (pintype "passive"))
      (node (ref "IC7") (pin "4") (pinfunction "REFOUT_4") (pintype "output"))
    )
    (net (code "32") (name "Net-(IC7-REGCAPA)") (class "Default")
      (node (ref "C48") (pin "2") (pinfunction "2_2") (pintype "passive"))
      (node (ref "C49") (pin "1") (pinfunction "1_1") (pintype "passive"))
      (node (ref "IC7") (pin "5") (pinfunction "REGCAPA_5") (pintype "output"))
    )
    (net (code "33") (name "Net-(IC7-REGCAPD)") (class "Default")
      (node (ref "C50") (pin "2") (pinfunction "2_2") (pintype "passive"))
      (node (ref "C51") (pin "1") (pinfunction "1_1") (pintype "passive"))
      (node (ref "IC7") (pin "18") (pinfunction "REGCAPD_18") (pintype "output"))
    )
    (net (code "34") (name "P3V3IO") (class "Default")
      (node (ref "R38") (pin "2") (pinfunction "2_2") (pintype "passive"))
    )
    (net (code "35") (name "P5V0A") (class "Default")
      (node (ref "D13") (pin "1") (pinfunction "C_1") (pintype "passive"))
      (node (ref "D14") (pin "1") (pinfunction "C_1") (pintype "passive"))
      (node (ref "D17") (pin "1") (pinfunction "C_1") (pintype "passive"))
      (node (ref "D18") (pin "1") (pinfunction "C_1") (pintype "passive"))
      (node (ref "D29") (pin "1") (pinfunction "C_1") (pintype "passive"))
      (node (ref "D30") (pin "1") (pinfunction "C_1") (pintype "passive"))
      (node (ref "D31") (pin "1") (pinfunction "C_1") (pintype "passive"))
      (node (ref "R37") (pin "2") (pinfunction "2_2") (pintype "passive"))
    )
    (net (code "36") (name "unconnected-(IC7-XTAL1-Pad9)") (class "Default")
      (node (ref "IC7") (pin "9") (pinfunction "XTAL1_9") (pintype "input+no_connect"))
    )
  )
)
